# Cube_Controller.net
KiCad netlist of a schematic drawn in Altium Designer
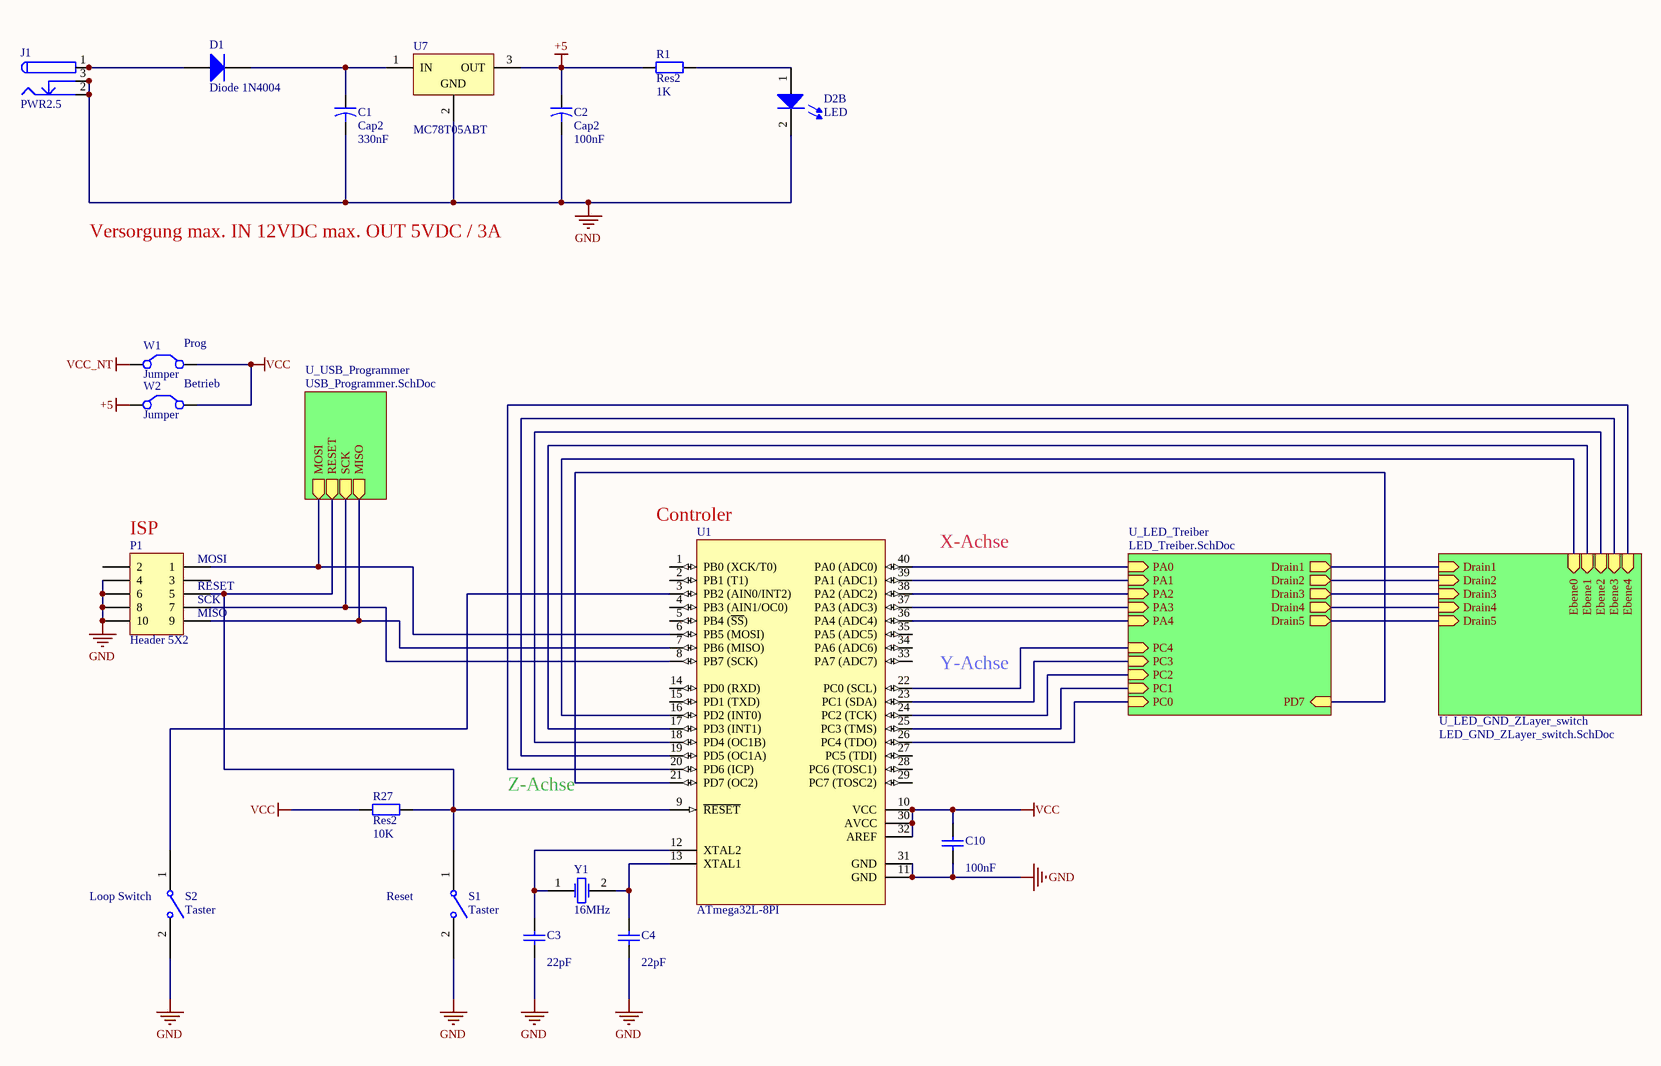
[diagram p0: Cube_Controller.SchDoc]

(export (version "E")
  (design (tool "Eeschema 10.0.6"))
  (components
    (comp (ref "C1")
      (value "Cap2")
      (footprint "Miscellaneous Devices:RAD-0.1")
      (description "Capacitor")
      (fields (field (name "ALTIUM_VALUE") "330nF") (field (name "PUBLISHER") "Altium Limited"))
      (libsource (lib "Miscellaneous Devices") (part "Cap2"))
    )
    (comp (ref "C2")
      (value "Cap2")
      (footprint "Miscellaneous Devices:RAD-0.1")
      (description "Capacitor")
      (fields (field (name "ALTIUM_VALUE") "100nF") (field (name "PUBLISHER") "Altium Limited"))
      (libsource (lib "Miscellaneous Devices") (part "Cap2"))
    )
    (comp (ref "C3")
      (value "22pF")
      (footprint "Miscellaneous Devices:RAD-0.1")
      (description "Capacitor (Semiconductor SIM Model)")
      (fields (field (name "Comment") "Cap Semi") (field (name "PUBLISHER") "Altium Limited"))
      (libsource (lib "Miscellaneous Devices") (part "Cap Semi"))
    )
    (comp (ref "C4")
      (value "22pF")
      (footprint "Miscellaneous Devices:RAD-0.1")
      (description "Capacitor (Semiconductor SIM Model)")
      (fields (field (name "Comment") "Cap Semi") (field (name "PUBLISHER") "Altium Limited"))
      (libsource (lib "Miscellaneous Devices") (part "Cap Semi"))
    )
    (comp (ref "C10")
      (value "100nF")
      (footprint "Miscellaneous Devices:RAD-0.1")
      (description "Capacitor")
      (fields (field (name "Comment") "Cap") (field (name "PUBLISHER") "Altium Limited"))
      (libsource (lib "Miscellaneous Devices") (part "Cap"))
    )
    (comp (ref "D1")
      (value "Diode 1N4004")
      (footprint "DO-41")
      (description "1 Amp General Purpose Rectifier")
      (fields (field (name "PUBLISHER") "Altium Limited"))
      (libsource (lib "Miscellaneous Devices") (part "Diode 1N4004"))
    )
    (comp (ref "D2")
      (value "LED")
      (footprint "LED 3mm")
      (description "LED bedrahtet")
      (libsource (lib "StdBT") (part "LED Std"))
    )
    (comp (ref "J1")
      (value "PWR2.5")
      (footprint "KLD-0202")
      (description "Low Voltage Power Supply Connector")
      (fields (field (name "PUBLISHER") "Altium Limited"))
      (libsource (lib "Miscellaneous Connectors") (part "PWR2.5"))
    )
    (comp (ref "P1")
      (value "Header 5X2")
      (footprint "HDR2X5")
      (description "Header, 5-Pin, Dual row")
      (fields (field (name "PUBLISHER") "Altium Limited"))
      (libsource (lib "Miscellaneous Connectors") (part "Header 5X2"))
    )
    (comp (ref "R1")
      (value "Res2")
      (footprint "AXIAL-0.4")
      (description "Resistor")
      (fields (field (name "ALTIUM_VALUE") "1K") (field (name "PUBLISHER") "Altium Limited"))
      (libsource (lib "Miscellaneous Devices") (part "Res2"))
    )
    (comp (ref "R27")
      (value "Res2")
      (footprint "AXIAL-0.4")
      (description "Resistor")
      (fields (field (name "ALTIUM_VALUE") "10K") (field (name "PUBLISHER") "Altium Limited"))
      (libsource (lib "Miscellaneous Devices") (part "Res2"))
    )
    (comp (ref "S1") (value "Taster") (footprint "StdBT:Taster") (libsource (lib "StdBT") (part "Taster")))
    (comp (ref "S2") (value "Taster") (footprint "StdBT:Taster") (libsource (lib "StdBT") (part "Taster")))
    (comp (ref "U1")
      (value "ATmega32L-8PI")
      (footprint "40P6")
      (description "8-Bit AVR Microcontroller with 32K Bytes of In-System Programmable Flash Memory")
      (fields (field (name "PUBLISHER") "Altium Limited"))
      (libsource (lib "Atmel Microcontroller 8-Bit AVR") (part "ATmega32L-8PI"))
    )
    (comp (ref "U7")
      (value "MC78T05ABT")
      (footprint "221A-04")
      (description "Three-Ampere Positive Fixed Voltage Regulator")
      (fields (field (name "PUBLISHER") "Altium Limited"))
      (libsource (lib "Motorola Power Mgt Voltage Regulator") (part "MC78T05ABT"))
    )
    (comp (ref "W1")
      (value "Jumper")
      (footprint "Miscellaneous Connectors:HDR1X2")
      (description "Jumper Wire")
      (fields (field (name "PUBLISHER") "Altium Limited"))
      (libsource (lib "Miscellaneous Devices") (part "Jumper"))
    )
    (comp (ref "W2")
      (value "Jumper")
      (footprint "Miscellaneous Connectors:HDR1X2")
      (description "Jumper Wire")
      (fields (field (name "PUBLISHER") "Altium Limited"))
      (libsource (lib "Miscellaneous Devices") (part "Jumper"))
    )
    (comp (ref "Y1")
      (value "16MHz")
      (footprint "Quarz HC49-4HL")
      (libsource (lib "StdBT") (part "Quarz HC49-4HL"))
    )
  )
  (nets
    (net (code "1") (name "+5") (class "Default")
      (node (ref "C2") (pin "1") (pinfunction "1_1") (pintype "passive"))
      (node (ref "R1") (pin "1") (pinfunction "1_1") (pintype "passive"))
      (node (ref "U7") (pin "3") (pinfunction "OUT_3") (pintype "power_in"))
      (node (ref "W2") (pin "1") (pinfunction "C1_1") (pintype "passive"))
    )
    (net (code "7") (name "/Ebene0") (class "Default")
      (node (ref "U1") (pin "16") (pinfunction "PD2_(INT0)_16") (pintype "bidirectional"))
    )
    (net (code "8") (name "/Ebene1") (class "Default")
      (node (ref "U1") (pin "17") (pinfunction "PD3_(INT1)_17") (pintype "bidirectional"))
    )
    (net (code "9") (name "/Ebene2") (class "Default")
      (node (ref "U1") (pin "18") (pinfunction "PD4_(OC1B)_18") (pintype "bidirectional"))
    )
    (net (code "10") (name "/Ebene3") (class "Default")
      (node (ref "U1") (pin "19") (pinfunction "PD5_(OC1A)_19") (pintype "bidirectional"))
    )
    (net (code "11") (name "/Ebene4") (class "Default")
      (node (ref "U1") (pin "20") (pinfunction "PD6_(ICP)_20") (pintype "bidirectional"))
    )
    (net (code "12") (name "/MISO") (class "Default")
      (node (ref "P1") (pin "9") (pinfunction "9_9") (pintype "passive"))
      (node (ref "U1") (pin "7") (pinfunction "PB6_(MISO)_7") (pintype "bidirectional"))
    )
    (net (code "13") (name "/MOSI") (class "Default")
      (node (ref "P1") (pin "1") (pinfunction "1_1") (pintype "passive"))
      (node (ref "U1") (pin "6") (pinfunction "PB5_(MOSI)_6") (pintype "bidirectional"))
    )
    (net (code "14") (name "/PA0") (class "Default")
      (node (ref "U1") (pin "40") (pinfunction "PA0_(ADC0)_40") (pintype "bidirectional"))
    )
    (net (code "15") (name "/PA1") (class "Default")
      (node (ref "U1") (pin "39") (pinfunction "PA1_(ADC1)_39") (pintype "bidirectional"))
    )
    (net (code "16") (name "/PA2") (class "Default")
      (node (ref "U1") (pin "38") (pinfunction "PA2_(ADC2)_38") (pintype "bidirectional"))
    )
    (net (code "17") (name "/PA3") (class "Default")
      (node (ref "U1") (pin "37") (pinfunction "PA3_(ADC3)_37") (pintype "bidirectional"))
    )
    (net (code "18") (name "/PA4") (class "Default")
      (node (ref "U1") (pin "36") (pinfunction "PA4_(ADC4)_36") (pintype "bidirectional"))
    )
    (net (code "19") (name "/PC0") (class "Default")
      (node (ref "U1") (pin "26") (pinfunction "PC4_(TDO)_26") (pintype "bidirectional"))
    )
    (net (code "20") (name "/PC1") (class "Default")
      (node (ref "U1") (pin "25") (pinfunction "PC3_(TMS)_25") (pintype "bidirectional"))
    )
    (net (code "21") (name "/PC2") (class "Default")
      (node (ref "U1") (pin "24") (pinfunction "PC2_(TCK)_24") (pintype "bidirectional"))
    )
    (net (code "22") (name "/PC3") (class "Default")
      (node (ref "U1") (pin "23") (pinfunction "PC1_(SDA)_23") (pintype "bidirectional"))
    )
    (net (code "23") (name "/PC4") (class "Default")
      (node (ref "U1") (pin "22") (pinfunction "PC0_(SCL)_22") (pintype "bidirectional"))
    )
    (net (code "24") (name "/PD7") (class "Default")
      (node (ref "U1") (pin "21") (pinfunction "PD7_(OC2)_21") (pintype "bidirectional"))
    )
    (net (code "25") (name "/RESET") (class "Default")
      (node (ref "P1") (pin "5") (pinfunction "5_5") (pintype "passive"))
      (node (ref "R27") (pin "2") (pinfunction "2_2") (pintype "passive"))
      (node (ref "S1") (pin "1") (pinfunction "1_1") (pintype "passive"))
      (node (ref "U1") (pin "9") (pinfunction "~{RESET}_9") (pintype "input"))
    )
    (net (code "26") (name "/SCK") (class "Default")
      (node (ref "P1") (pin "7") (pinfunction "7_7") (pintype "passive"))
      (node (ref "U1") (pin "8") (pinfunction "PB7_(SCK)_8") (pintype "bidirectional"))
    )
    (net (code "27") (name "GND") (class "Default")
      (node (ref "C1") (pin "2") (pinfunction "2_2") (pintype "passive"))
      (node (ref "C10") (pin "1") (pinfunction "1_1") (pintype "passive"))
      (node (ref "C2") (pin "2") (pinfunction "2_2") (pintype "passive"))
      (node (ref "C3") (pin "1") (pinfunction "1_1") (pintype "passive"))
      (node (ref "C4") (pin "1") (pinfunction "1_1") (pintype "passive"))
      (node (ref "D2") (pin "2") (pintype "passive"))
      (node (ref "J1") (pin "2") (pinfunction "2_2") (pintype "power_in"))
      (node (ref "J1") (pin "2A") (pinfunction "2A_2A") (pintype "power_in"))
      (node (ref "J1") (pin "2B") (pinfunction "2B_2B") (pintype "power_in"))
      (node (ref "J1") (pin "3") (pinfunction "3_3") (pintype "power_in"))
      (node (ref "J1") (pin "3A") (pinfunction "3A_3A") (pintype "power_in"))
      (node (ref "J1") (pin "3B") (pinfunction "3B_3B") (pintype "power_in"))
      (node (ref "P1") (pin "10") (pinfunction "10_10") (pintype "passive"))
      (node (ref "P1") (pin "4") (pinfunction "4_4") (pintype "passive"))
      (node (ref "P1") (pin "6") (pinfunction "6_6") (pintype "passive"))
      (node (ref "P1") (pin "8") (pinfunction "8_8") (pintype "passive"))
      (node (ref "S1") (pin "2") (pinfunction "2_2") (pintype "passive"))
      (node (ref "S2") (pin "2") (pinfunction "2_2") (pintype "passive"))
      (node (ref "U1") (pin "11") (pinfunction "GND_11") (pintype "power_in"))
      (node (ref "U1") (pin "31") (pinfunction "GND_31") (pintype "power_in"))
      (node (ref "U7") (pin "2") (pinfunction "GND_2") (pintype "power_in"))
    )
    (net (code "28") (name "Net-(D1-A)") (class "Default")
      (node (ref "D1") (pin "1") (pinfunction "A_1") (pintype "passive"))
      (node (ref "J1") (pin "1") (pinfunction "1_1") (pintype "power_in"))
      (node (ref "J1") (pin "1A") (pinfunction "1A_1A") (pintype "power_in"))
      (node (ref "J1") (pin "1B") (pinfunction "1B_1B") (pintype "power_in"))
    )
    (net (code "29") (name "Net-(D1-K)") (class "Default")
      (node (ref "C1") (pin "1") (pinfunction "1_1") (pintype "passive"))
      (node (ref "D1") (pin "2") (pinfunction "K_2") (pintype "passive"))
      (node (ref "U7") (pin "1") (pinfunction "IN_1") (pintype "power_in"))
    )
    (net (code "30") (name "Net-(D2-Pad1)") (class "Default")
      (node (ref "D2") (pin "1") (pintype "passive"))
      (node (ref "R1") (pin "2") (pinfunction "2_2") (pintype "passive"))
    )
    (net (code "31") (name "Net-(U1-PB2_(AIN0{slash}INT2))") (class "Default")
      (node (ref "S2") (pin "1") (pinfunction "1_1") (pintype "passive"))
      (node (ref "U1") (pin "3") (pinfunction "PB2_(AIN0/INT2)_3") (pintype "bidirectional"))
    )
    (net (code "32") (name "Net-(U1-XTAL1)") (class "Default")
      (node (ref "C4") (pin "2") (pinfunction "2_2") (pintype "passive"))
      (node (ref "U1") (pin "13") (pinfunction "XTAL1_13") (pintype "passive"))
      (node (ref "Y1") (pin "2") (pinfunction "2_2") (pintype "passive"))
    )
    (net (code "33") (name "Net-(U1-XTAL2)") (class "Default")
      (node (ref "C3") (pin "2") (pinfunction "2_2") (pintype "passive"))
      (node (ref "U1") (pin "12") (pinfunction "XTAL2_12") (pintype "passive"))
      (node (ref "Y1") (pin "1") (pinfunction "1_1") (pintype "passive"))
    )
    (net (code "34") (name "VCC") (class "Default")
      (node (ref "C10") (pin "2") (pinfunction "2_2") (pintype "passive"))
      (node (ref "R27") (pin "1") (pinfunction "1_1") (pintype "passive"))
      (node (ref "U1") (pin "10") (pinfunction "VCC_10") (pintype "power_in"))
      (node (ref "U1") (pin "30") (pinfunction "AVCC_30") (pintype "power_in"))
      (node (ref "U1") (pin "32") (pinfunction "AREF_32") (pintype "passive"))
      (node (ref "W1") (pin "2") (pinfunction "C2_2") (pintype "passive"))
      (node (ref "W2") (pin "2") (pinfunction "C2_2") (pintype "passive"))
    )
    (net (code "35") (name "VCC_NT") (class "Default")
      (node (ref "W1") (pin "1") (pinfunction "C1_1") (pintype "passive"))
    )
    (net (code "36") (name "unconnected-(P1-Pad2)") (class "Default")
      (node (ref "P1") (pin "2") (pinfunction "2_2") (pintype "passive"))
    )
    (net (code "37") (name "unconnected-(P1-Pad3)") (class "Default")
      (node (ref "P1") (pin "3") (pinfunction "3_3") (pintype "passive"))
    )
    (net (code "38") (name "unconnected-(U1-PA5_(ADC5)-Pad35)") (class "Default")
      (node (ref "U1") (pin "35") (pinfunction "PA5_(ADC5)_35") (pintype "bidirectional"))
    )
    (net (code "39") (name "unconnected-(U1-PA6_(ADC6)-Pad34)") (class "Default")
      (node (ref "U1") (pin "34") (pinfunction "PA6_(ADC6)_34") (pintype "bidirectional"))
    )
    (net (code "40") (name "unconnected-(U1-PA7_(ADC7)-Pad33)") (class "Default")
      (node (ref "U1") (pin "33") (pinfunction "PA7_(ADC7)_33") (pintype "bidirectional"))
    )
    (net (code "41") (name "unconnected-(U1-PB0_(XCK{slash}T0)-Pad1)") (class "Default")
      (node (ref "U1") (pin "1") (pinfunction "PB0_(XCK/T0)_1") (pintype "bidirectional"))
    )
    (net (code "42") (name "unconnected-(U1-PB1_(T1)-Pad2)") (class "Default")
      (node (ref "U1") (pin "2") (pinfunction "PB1_(T1)_2") (pintype "bidirectional"))
    )
    (net (code "43") (name "unconnected-(U1-PB3_(AIN1{slash}OC0)-Pad4)") (class "Default")
      (node (ref "U1") (pin "4") (pinfunction "PB3_(AIN1/OC0)_4") (pintype "bidirectional"))
    )
    (net (code "44") (name "unconnected-(U1-PB4_(~{SS})-Pad5)") (class "Default")
      (node (ref "U1") (pin "5") (pinfunction "PB4_(~{SS})_5") (pintype "bidirectional"))
    )
    (net (code "45") (name "unconnected-(U1-PC5_(TDI)-Pad27)") (class "Default")
      (node (ref "U1") (pin "27") (pinfunction "PC5_(TDI)_27") (pintype "bidirectional"))
    )
    (net (code "46") (name "unconnected-(U1-PC6_(TOSC1)-Pad28)") (class "Default")
      (node (ref "U1") (pin "28") (pinfunction "PC6_(TOSC1)_28") (pintype "bidirectional"))
    )
    (net (code "47") (name "unconnected-(U1-PC7_(TOSC2)-Pad29)") (class "Default")
      (node (ref "U1") (pin "29") (pinfunction "PC7_(TOSC2)_29") (pintype "bidirectional"))
    )
    (net (code "48") (name "unconnected-(U1-PD0_(RXD)-Pad14)") (class "Default")
      (node (ref "U1") (pin "14") (pinfunction "PD0_(RXD)_14") (pintype "bidirectional"))
    )
    (net (code "49") (name "unconnected-(U1-PD1_(TXD)-Pad15)") (class "Default")
      (node (ref "U1") (pin "15") (pinfunction "PD1_(TXD)_15") (pintype "bidirectional"))
    )
  )
)
